# Backpage.net
KiCad netlist of a schematic drawn in Altium Designer
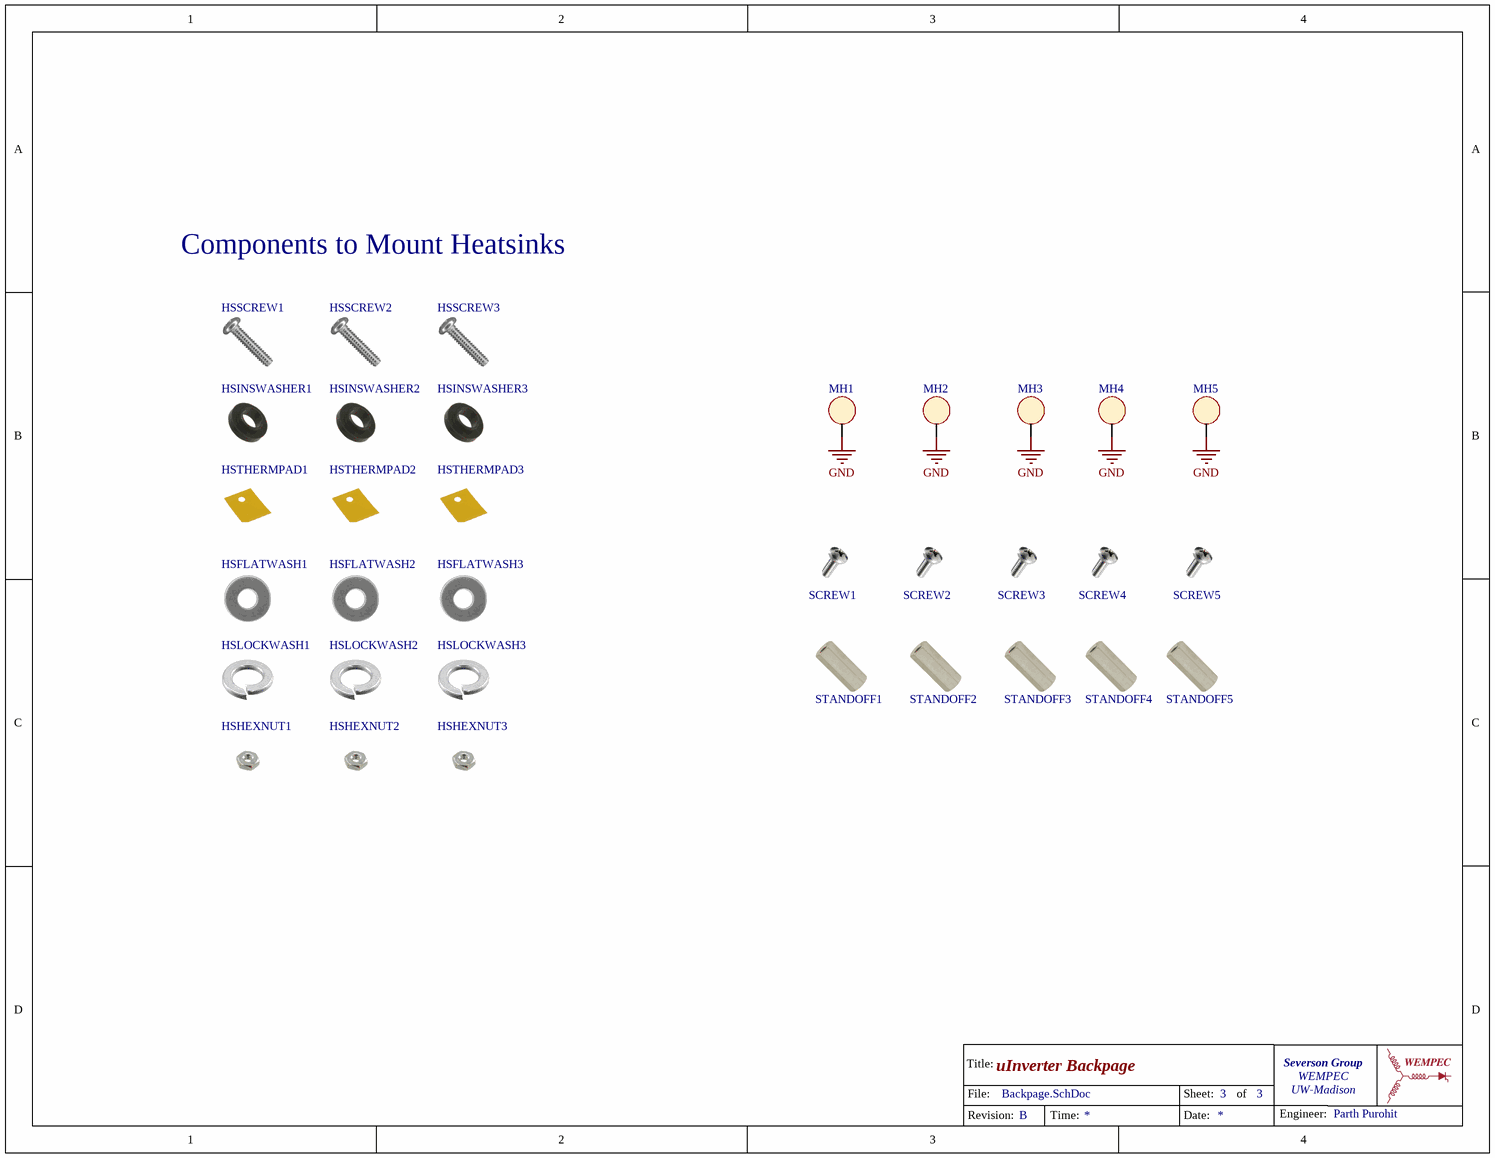
[diagram p0: Backpage.SchDoc]

(export (version "E")
  (design (tool "Eeschema 10.0.6"))
  (components
    (comp (ref "HSFLATWASH1")
      (value "FWSS 004")
      (description "WASHER FLAT #4 STAINLESS STEEL")
      (fields (field (name "MANUFACTURER") "B&F Fastener Supply"))
      (libsource (lib "Schlib_uInverter") (part "FWSS 004"))
    )
    (comp (ref "HSFLATWASH2")
      (value "FWSS 004")
      (description "WASHER FLAT #4 STAINLESS STEEL")
      (fields (field (name "MANUFACTURER") "B&F Fastener Supply"))
      (libsource (lib "Schlib_uInverter") (part "FWSS 004"))
    )
    (comp (ref "HSFLATWASH3")
      (value "FWSS 004")
      (description "WASHER FLAT #4 STAINLESS STEEL")
      (fields (field (name "MANUFACTURER") "B&F Fastener Supply"))
      (libsource (lib "Schlib_uInverter") (part "FWSS 004"))
    )
    (comp (ref "HSHEXNUT1")
      (value "HNZ 440")
      (description "HEX NUT 1/4in 4-40")
      (fields (field (name "MANUFACTURER") "B&F Fastener Supply"))
      (libsource (lib "Schlib_uInverter") (part "HNZ 440"))
    )
    (comp (ref "HSHEXNUT2")
      (value "HNZ 440")
      (description "HEX NUT 1/4in 4-40")
      (fields (field (name "MANUFACTURER") "B&F Fastener Supply"))
      (libsource (lib "Schlib_uInverter") (part "HNZ 440"))
    )
    (comp (ref "HSHEXNUT3")
      (value "HNZ 440")
      (description "HEX NUT 1/4in 4-40")
      (fields (field (name "MANUFACTURER") "B&F Fastener Supply"))
      (libsource (lib "Schlib_uInverter") (part "HNZ 440"))
    )
    (comp (ref "HSINSWASHER1")
      (value "7721-7PPSG")
      (description "WASHER SHOULDER #4 POLY SULFIDE")
      (fields (field (name "MANUFACTURER") "Boyd Laconia, LLC"))
      (libsource (lib "Schlib_uInverter") (part "7721-7PPSG"))
    )
    (comp (ref "HSINSWASHER2")
      (value "7721-7PPSG")
      (description "WASHER SHOULDER #4 POLY SULFIDE")
      (fields (field (name "MANUFACTURER") "Boyd Laconia, LLC"))
      (libsource (lib "Schlib_uInverter") (part "7721-7PPSG"))
    )
    (comp (ref "HSINSWASHER3")
      (value "7721-7PPSG")
      (description "WASHER SHOULDER #4 POLY SULFIDE")
      (fields (field (name "MANUFACTURER") "Boyd Laconia, LLC"))
      (libsource (lib "Schlib_uInverter") (part "7721-7PPSG"))
    )
    (comp (ref "HSLOCKWASH1")
      (value "4693")
      (description "WASHER SPLIT LOCK #4 STEEL")
      (fields (field (name "MANUFACTURER") "Keystone Electronics"))
      (libsource (lib "Schlib_uInverter") (part "4693"))
    )
    (comp (ref "HSLOCKWASH2")
      (value "4693")
      (description "WASHER SPLIT LOCK #4 STEEL")
      (fields (field (name "MANUFACTURER") "Keystone Electronics"))
      (libsource (lib "Schlib_uInverter") (part "4693"))
    )
    (comp (ref "HSLOCKWASH3")
      (value "4693")
      (description "WASHER SPLIT LOCK #4 STEEL")
      (fields (field (name "MANUFACTURER") "Keystone Electronics"))
      (libsource (lib "Schlib_uInverter") (part "4693"))
    )
    (comp (ref "HSSCREW1")
      (value "PMSSS4400050PH")
      (description "MACHINE SCREW PAN PHILLIPS 4-40")
      (fields
        (field (name "MANUFACTURER PART NUMBER") "PMSSS 440 0050 PH")
        (field (name "MANUFACTURER") "B&F Fastener Supply")
      )
      (libsource (lib "Schlib_uInverter") (part "PMSSS4400050PH"))
    )
    (comp (ref "HSSCREW2")
      (value "PMSSS4400050PH")
      (description "MACHINE SCREW PAN PHILLIPS 4-40")
      (fields
        (field (name "MANUFACTURER PART NUMBER") "PMSSS 440 0050 PH")
        (field (name "MANUFACTURER") "B&F Fastener Supply")
      )
      (libsource (lib "Schlib_uInverter") (part "PMSSS4400050PH"))
    )
    (comp (ref "HSSCREW3")
      (value "PMSSS4400050PH")
      (description "MACHINE SCREW PAN PHILLIPS 4-40")
      (fields
        (field (name "MANUFACTURER PART NUMBER") "PMSSS 440 0050 PH")
        (field (name "MANUFACTURER") "B&F Fastener Supply")
      )
      (libsource (lib "Schlib_uInverter") (part "PMSSS4400050PH"))
    )
    (comp (ref "HSTHERMPAD1")
      (value "43-77-9G")
      (description "THERM PAD 18.42MMX13.21MM AMBER")
      (fields (field (name "MANUFACTURER") "Boyd Laconia, LLC"))
      (libsource (lib "Schlib_uInverter") (part "43-77-9G"))
    )
    (comp (ref "HSTHERMPAD2")
      (value "43-77-9G")
      (description "THERM PAD 18.42MMX13.21MM AMBER")
      (fields (field (name "MANUFACTURER") "Boyd Laconia, LLC"))
      (libsource (lib "Schlib_uInverter") (part "43-77-9G"))
    )
    (comp (ref "HSTHERMPAD3")
      (value "43-77-9G")
      (description "THERM PAD 18.42MMX13.21MM AMBER")
      (fields (field (name "MANUFACTURER") "Boyd Laconia, LLC"))
      (libsource (lib "Schlib_uInverter") (part "43-77-9G"))
    )
    (comp (ref "MH1")
      (value "MOUNT_HOLE")
      (footprint "MOUNTING_HOLE")
      (description "MOUNTING HOLE")
      (libsource (lib "Schlib_uInv01") (part "MOUNT_HOLE"))
    )
    (comp (ref "MH2")
      (value "MOUNT_HOLE")
      (footprint "MOUNTING_HOLE")
      (description "MOUNTING HOLE")
      (libsource (lib "Schlib_uInv01") (part "MOUNT_HOLE"))
    )
    (comp (ref "MH3")
      (value "MOUNT_HOLE")
      (footprint "MOUNTING_HOLE")
      (description "MOUNTING HOLE")
      (libsource (lib "Schlib_uInv01") (part "MOUNT_HOLE"))
    )
    (comp (ref "MH4")
      (value "MOUNT_HOLE")
      (footprint "MOUNTING_HOLE")
      (description "MOUNTING HOLE")
      (libsource (lib "Schlib_uInv01") (part "MOUNT_HOLE"))
    )
    (comp (ref "MH5")
      (value "MOUNT_HOLE")
      (footprint "MOUNTING_HOLE")
      (description "MOUNTING HOLE")
      (libsource (lib "Schlib_uInv01") (part "MOUNT_HOLE"))
    )
    (comp (ref "SCREW1")
      (value "Screw-4-40")
      (description "MACH SCREW PAN PHILLIPS #4-40")
      (fields
        (field (name "MANUFACTURER PART NUMBER") "9900")
        (field (name "MANUFACTURER") "Keystone Electronics")
      )
      (libsource (lib "Schlib_uInverter") (part "Screw-4-40"))
    )
    (comp (ref "SCREW2")
      (value "Screw-4-40")
      (description "MACH SCREW PAN PHILLIPS #4-40")
      (fields
        (field (name "MANUFACTURER PART NUMBER") "9900")
        (field (name "MANUFACTURER") "Keystone Electronics")
      )
      (libsource (lib "Schlib_uInverter") (part "Screw-4-40"))
    )
    (comp (ref "SCREW3")
      (value "Screw-4-40")
      (description "MACH SCREW PAN PHILLIPS #4-40")
      (fields
        (field (name "MANUFACTURER PART NUMBER") "9900")
        (field (name "MANUFACTURER") "Keystone Electronics")
      )
      (libsource (lib "Schlib_uInverter") (part "Screw-4-40"))
    )
    (comp (ref "SCREW4")
      (value "Screw-4-40")
      (description "MACH SCREW PAN PHILLIPS #4-40")
      (fields
        (field (name "MANUFACTURER PART NUMBER") "9900")
        (field (name "MANUFACTURER") "Keystone Electronics")
      )
      (libsource (lib "Schlib_uInverter") (part "Screw-4-40"))
    )
    (comp (ref "SCREW5")
      (value "Screw-4-40")
      (description "MACH SCREW PAN PHILLIPS #4-40")
      (fields
        (field (name "MANUFACTURER PART NUMBER") "9900")
        (field (name "MANUFACTURER") "Keystone Electronics")
      )
      (libsource (lib "Schlib_uInverter") (part "Screw-4-40"))
    )
    (comp (ref "STANDOFF1")
      (value "Standoff-4-40")
      (description "HEX STANDOFF #4-40 BRASS 1/2\"")
      (fields
        (field (name "MANUFACTURER PART NUMBER") "1656")
        (field (name "MANUFACTURER") "Keystone Electronics")
      )
      (libsource (lib "Schlib_uInverter") (part "Standoff-4-40"))
    )
    (comp (ref "STANDOFF2")
      (value "Standoff-4-40")
      (description "HEX STANDOFF #4-40 BRASS 1/2\"")
      (fields
        (field (name "MANUFACTURER PART NUMBER") "1656")
        (field (name "MANUFACTURER") "Keystone Electronics")
      )
      (libsource (lib "Schlib_uInverter") (part "Standoff-4-40"))
    )
    (comp (ref "STANDOFF3")
      (value "Standoff-4-40")
      (description "HEX STANDOFF #4-40 BRASS 1/2\"")
      (fields
        (field (name "MANUFACTURER PART NUMBER") "1656")
        (field (name "MANUFACTURER") "Keystone Electronics")
      )
      (libsource (lib "Schlib_uInverter") (part "Standoff-4-40"))
    )
    (comp (ref "STANDOFF4")
      (value "Standoff-4-40")
      (description "HEX STANDOFF #4-40 BRASS 1/2\"")
      (fields
        (field (name "MANUFACTURER PART NUMBER") "1656")
        (field (name "MANUFACTURER") "Keystone Electronics")
      )
      (libsource (lib "Schlib_uInverter") (part "Standoff-4-40"))
    )
    (comp (ref "STANDOFF5")
      (value "Standoff-4-40")
      (description "HEX STANDOFF #4-40 BRASS 1/2\"")
      (fields
        (field (name "MANUFACTURER PART NUMBER") "1656")
        (field (name "MANUFACTURER") "Keystone Electronics")
      )
      (libsource (lib "Schlib_uInverter") (part "Standoff-4-40"))
    )
    (comp (ref "TitleBlockWEMPEC3")
      (value "TitleBlockWEMPEC")
      (libsource (lib "Schlib_uInv01") (part "TitleBlockWEMPEC"))
    )
  )
  (nets
    (net (code "1") (name "GND") (class "Default")
      (node (ref "MH1") (pin "1") (pinfunction "1_1") (pintype "passive"))
      (node (ref "MH2") (pin "1") (pinfunction "1_1") (pintype "passive"))
      (node (ref "MH3") (pin "1") (pinfunction "1_1") (pintype "passive"))
      (node (ref "MH4") (pin "1") (pinfunction "1_1") (pintype "passive"))
      (node (ref "MH5") (pin "1") (pinfunction "1_1") (pintype "passive"))
    )
  )
)
